# p7_1_3v3_-_Adafruit_Battery.net
KiCad netlist of a schematic drawn in EAGLE
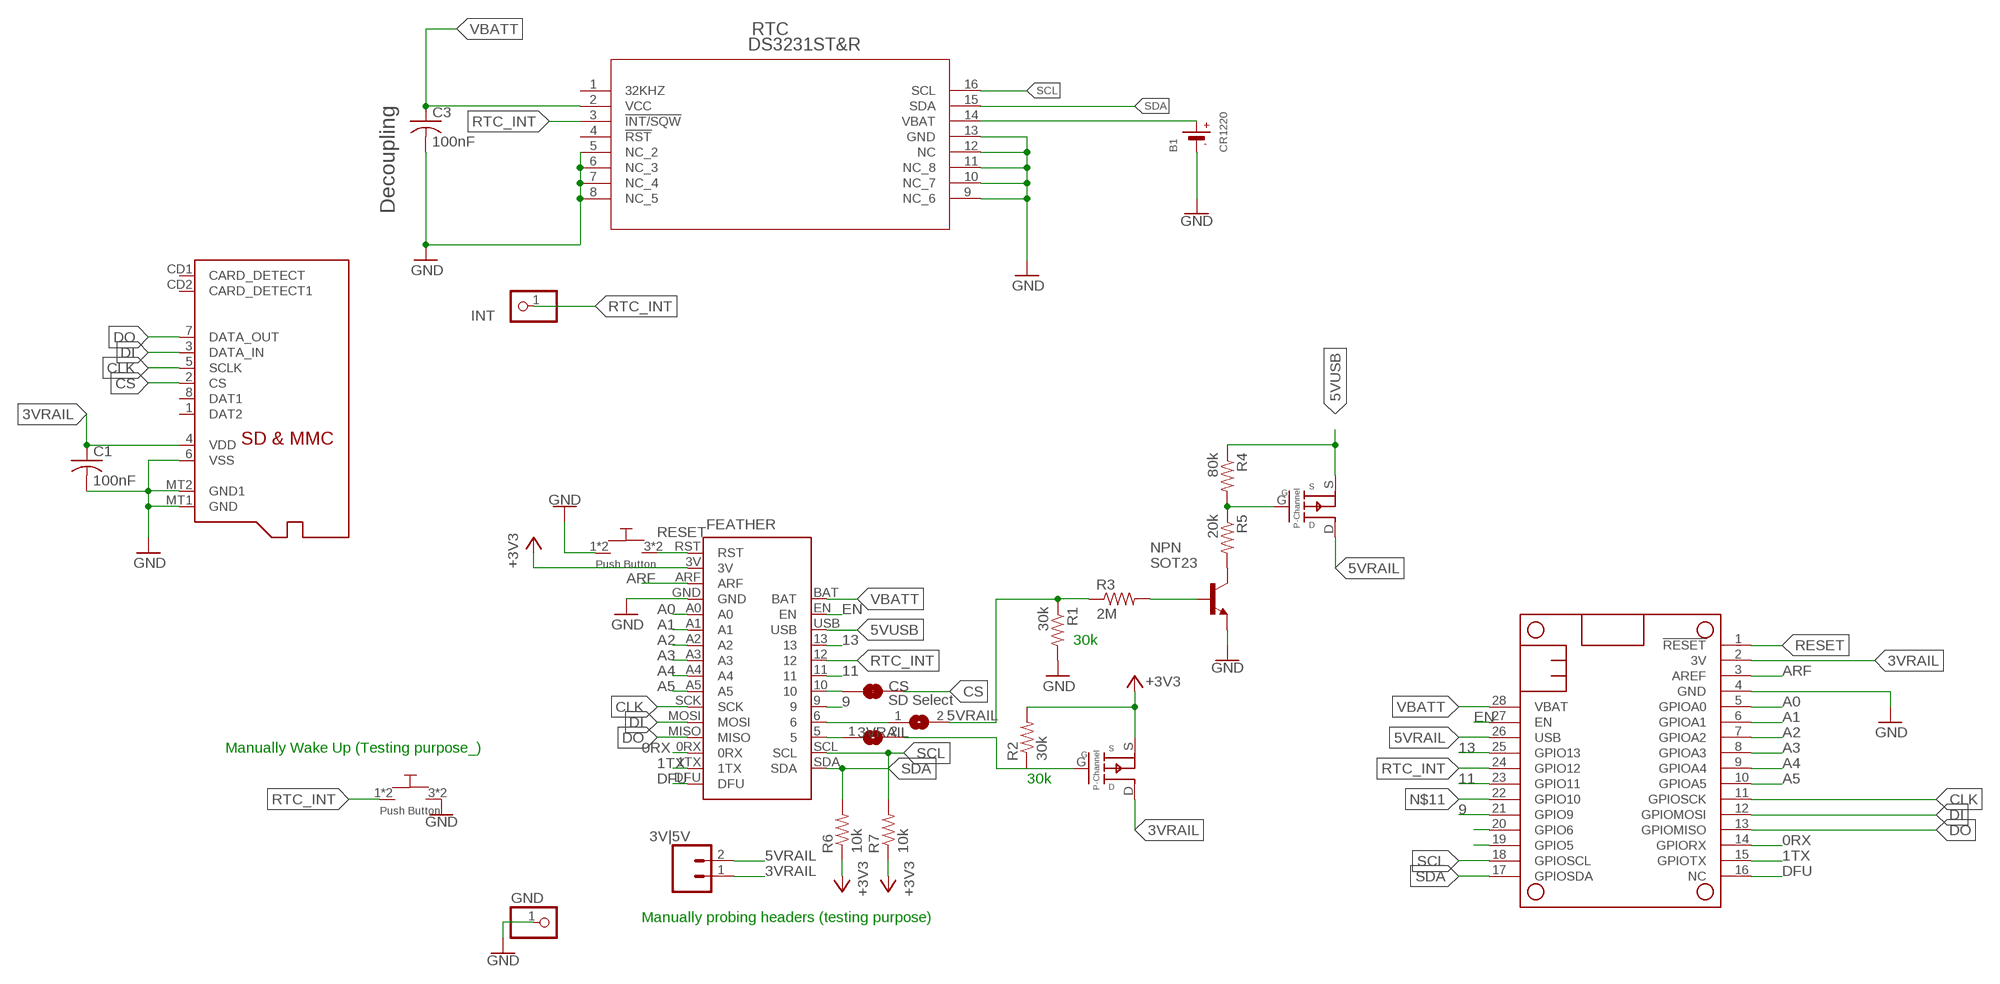
[diagram p0: schematic, sheet 1]

(export (version "E")
  (design (tool "Eeschema 10.0.6"))
  (components
    (comp (ref "3VRAIL")
      (value "SJ")
      (footprint "eagle-import:SJ")
      (libsource (lib "eagle-import") (part "SJ"))
    )
    (comp (ref "3V|5V")
      (value "CONN_021X02_NO_SILK")
      (footprint "eagle-import:1X02_NO_SILK")
      (libsource (lib "eagle-import") (part "CONN_021X02_NO_SILK"))
    )
    (comp (ref "5VRAIL")
      (value "SJ")
      (footprint "eagle-import:SJ")
      (libsource (lib "eagle-import") (part "SJ"))
    )
    (comp (ref "B1")
      (value "CR1220")
      (footprint "eagle-import:CR1220")
      (libsource (lib "eagle-import") (part "BATTERYCR1220_SMT"))
    )
    (comp (ref "C1")
      (value "100nF")
      (footprint "eagle-import:C1206")
      (libsource (lib "eagle-import") (part "C-USC1206"))
    )
    (comp (ref "C3")
      (value "100nF")
      (footprint "eagle-import:C1206")
      (libsource (lib "eagle-import") (part "C-USC1206"))
    )
    (comp (ref "CS")
      (value "SD Select")
      (footprint "eagle-import:SMT-JUMPER_2_NC_TRACE_SILK")
      (libsource (lib "eagle-import") (part "JUMPER-SMT_2_NC_TRACE_SILK"))
    )
    (comp (ref "FEATHER")
      (value "BLUEFRUIT_M0")
      (footprint "eagle-import:BLUEFRUIT_MO")
      (libsource (lib "eagle-import") (part "BLUEFRUIT_M0"))
    )
    (comp (ref "GND")
      (value "PINHD-1X1")
      (footprint "eagle-import:1X01")
      (libsource (lib "eagle-import") (part "adafruitmodified_PINHD-1X1"))
    )
    (comp (ref "INT")
      (value "PINHD-1X1CB")
      (footprint "eagle-import:1X01-CLEANBIG")
      (libsource (lib "eagle-import") (part "PINHD-1X1CB"))
    )
    (comp (ref "MICROSD")
      (value "MICROSD")
      (footprint "eagle-import:MICROSD")
      (libsource (lib "eagle-import") (part "MICROSD"))
    )
    (comp (ref "MS1")
      (value "FEATHERWING")
      (footprint "eagle-import:FEATHERWING")
      (libsource (lib "eagle-import") (part "FEATHERWING"))
    )
    (comp (ref "NPN")
      (value "SOT23")
      (footprint "eagle-import:SOT23")
      (libsource (lib "eagle-import") (part "BC849"))
    )
    (comp (ref "PMOS1")
      (value "SSM3J3228R")
      (footprint "eagle-import:SOT-23-3")
      (libsource (lib "eagle-import") (part "SSM3J3228R"))
    )
    (comp (ref "PMOS2")
      (value "SSM3J3228R")
      (footprint "eagle-import:SOT-23-3")
      (libsource (lib "eagle-import") (part "SSM3J3228R"))
    )
    (comp (ref "R1")
      (value "30k")
      (footprint "eagle-import:R1206")
      (libsource (lib "eagle-import") (part "R-US_R1206"))
    )
    (comp (ref "R2")
      (value "30k")
      (footprint "eagle-import:R1206")
      (libsource (lib "eagle-import") (part "R-US_R1206"))
    )
    (comp (ref "R3")
      (value "2M")
      (footprint "eagle-import:R1206")
      (libsource (lib "eagle-import") (part "R-US_R1206"))
    )
    (comp (ref "R4")
      (value "80k")
      (footprint "eagle-import:R1206")
      (libsource (lib "eagle-import") (part "R-US_R1206"))
    )
    (comp (ref "R5")
      (value "20k")
      (footprint "eagle-import:R1206")
      (libsource (lib "eagle-import") (part "R-US_R1206"))
    )
    (comp (ref "R6")
      (value "10k")
      (footprint "eagle-import:R1206")
      (libsource (lib "eagle-import") (part "R-US_R1206"))
    )
    (comp (ref "R7")
      (value "10k")
      (footprint "eagle-import:R1206")
      (libsource (lib "eagle-import") (part "R-US_R1206"))
    )
    (comp (ref "RTC")
      (value "DS3231ST&R")
      (footprint "eagle-import:21-0042B_16")
      (fields (field (name "MANUFACTURER_PART_NUMBER") "DS3231S#T&R"))
      (libsource (lib "eagle-import") (part "DS3231ST&R"))
    )
    (comp (ref "U$1")
      (value "PUSH_BUTTON")
      (footprint "eagle-import:PUSHBUTTON_SMD")
      (libsource (lib "eagle-import") (part "PUSH_BUTTON"))
    )
    (comp (ref "U$2")
      (value "PUSH_BUTTON")
      (footprint "eagle-import:PUSHBUTTON_SMD")
      (libsource (lib "eagle-import") (part "PUSH_BUTTON"))
    )
  )
  (nets
    (net (code "1") (name "+3V3") (class "Default")
      (node (ref "FEATHER") (pin "3V") (pinfunction "3V_3V") (pintype "bidirectional"))
      (node (ref "PMOS2") (pin "S") (pinfunction "S_S") (pintype "bidirectional"))
      (node (ref "R2") (pin "2") (pinfunction "2_2") (pintype "passive"))
      (node (ref "R6") (pin "1") (pinfunction "1_1") (pintype "passive"))
      (node (ref "R7") (pin "1") (pinfunction "1_1") (pintype "passive"))
    )
    (net (code "2") (name "/0RX") (class "Default")
      (node (ref "FEATHER") (pin "0RX") (pinfunction "0RX_0RX") (pintype "bidirectional"))
      (node (ref "MS1") (pin "14") (pinfunction "GPIORX_14") (pintype "bidirectional"))
    )
    (net (code "3") (name "/1TX") (class "Default")
      (node (ref "FEATHER") (pin "1TX") (pinfunction "1TX_1TX") (pintype "bidirectional"))
      (node (ref "MS1") (pin "15") (pinfunction "GPIOTX_15") (pintype "bidirectional"))
    )
    (net (code "4") (name "/9") (class "Default")
      (node (ref "FEATHER") (pin "9") (pinfunction "9_9") (pintype "bidirectional"))
      (node (ref "MS1") (pin "21") (pinfunction "GPIO9_21") (pintype "bidirectional"))
    )
    (net (code "5") (name "/11") (class "Default")
      (node (ref "FEATHER") (pin "11") (pinfunction "11_11") (pintype "bidirectional"))
      (node (ref "MS1") (pin "23") (pinfunction "GPIO11_23") (pintype "bidirectional"))
    )
    (net (code "6") (name "/13") (class "Default")
      (node (ref "FEATHER") (pin "13") (pinfunction "13_13") (pintype "bidirectional"))
      (node (ref "MS1") (pin "25") (pinfunction "GPIO13_25") (pintype "bidirectional"))
    )
    (net (code "7") (name "/A0") (class "Default")
      (node (ref "FEATHER") (pin "A0") (pinfunction "A0_A0") (pintype "bidirectional"))
      (node (ref "MS1") (pin "5") (pinfunction "GPIOA0_5") (pintype "bidirectional"))
    )
    (net (code "8") (name "/A1") (class "Default")
      (node (ref "FEATHER") (pin "A1") (pinfunction "A1_A1") (pintype "bidirectional"))
      (node (ref "MS1") (pin "6") (pinfunction "GPIOA1_6") (pintype "bidirectional"))
    )
    (net (code "9") (name "/A2") (class "Default")
      (node (ref "FEATHER") (pin "A2") (pinfunction "A2_A2") (pintype "bidirectional"))
      (node (ref "MS1") (pin "7") (pinfunction "GPIOA2_7") (pintype "bidirectional"))
    )
    (net (code "10") (name "/A3") (class "Default")
      (node (ref "FEATHER") (pin "A3") (pinfunction "A3_A3") (pintype "bidirectional"))
      (node (ref "MS1") (pin "8") (pinfunction "GPIOA3_8") (pintype "bidirectional"))
    )
    (net (code "11") (name "/A4") (class "Default")
      (node (ref "FEATHER") (pin "A4") (pinfunction "A4_A4") (pintype "bidirectional"))
      (node (ref "MS1") (pin "9") (pinfunction "GPIOA4_9") (pintype "bidirectional"))
    )
    (net (code "12") (name "/A5") (class "Default")
      (node (ref "FEATHER") (pin "A5") (pinfunction "A5_A5") (pintype "bidirectional"))
      (node (ref "MS1") (pin "10") (pinfunction "GPIOA5_10") (pintype "bidirectional"))
    )
    (net (code "13") (name "/ARF") (class "Default")
      (node (ref "FEATHER") (pin "ARF") (pinfunction "ARF_ARF") (pintype "bidirectional"))
      (node (ref "MS1") (pin "3") (pinfunction "AREF_3") (pintype "passive"))
    )
    (net (code "14") (name "/DFU") (class "Default")
      (node (ref "FEATHER") (pin "DFU") (pinfunction "DFU_DFU") (pintype "bidirectional"))
      (node (ref "MS1") (pin "16") (pinfunction "NC_16") (pintype "passive"))
    )
    (net (code "15") (name "/EN") (class "Default")
      (node (ref "FEATHER") (pin "EN") (pinfunction "EN_EN") (pintype "bidirectional"))
      (node (ref "MS1") (pin "27") (pinfunction "EN_27") (pintype "passive"))
    )
    (net (code "16") (name "3VRAIL") (class "Default")
      (node (ref "3V|5V") (pin "1") (pinfunction "1_1") (pintype "passive"))
      (node (ref "C1") (pin "1") (pinfunction "1_1") (pintype "passive"))
      (node (ref "MICROSD") (pin "4") (pinfunction "VDD_4") (pintype "power_in"))
      (node (ref "MS1") (pin "2") (pinfunction "3V_2") (pintype "power_in"))
      (node (ref "PMOS2") (pin "D") (pinfunction "D_D") (pintype "bidirectional"))
    )
    (net (code "17") (name "5VRAIL") (class "Default")
      (node (ref "3V|5V") (pin "2") (pinfunction "2_2") (pintype "passive"))
      (node (ref "MS1") (pin "26") (pinfunction "USB_26") (pintype "power_in"))
      (node (ref "PMOS1") (pin "D") (pinfunction "D_D") (pintype "bidirectional"))
    )
    (net (code "18") (name "5VUSB") (class "Default")
      (node (ref "FEATHER") (pin "USB") (pinfunction "USB_USB") (pintype "bidirectional"))
      (node (ref "PMOS1") (pin "S") (pinfunction "S_S") (pintype "bidirectional"))
      (node (ref "R4") (pin "1") (pinfunction "1_1") (pintype "passive"))
    )
    (net (code "19") (name "CLK") (class "Default")
      (node (ref "FEATHER") (pin "SCK") (pinfunction "SCK_SCK") (pintype "bidirectional"))
      (node (ref "MICROSD") (pin "5") (pinfunction "SCLK_5") (pintype "input"))
      (node (ref "MS1") (pin "11") (pinfunction "GPIOSCK_11") (pintype "bidirectional"))
    )
    (net (code "20") (name "CS") (class "Default")
      (node (ref "CS") (pin "2") (pinfunction "2_2") (pintype "passive"))
      (node (ref "MICROSD") (pin "2") (pinfunction "CS_2") (pintype "input"))
    )
    (net (code "21") (name "DI") (class "Default")
      (node (ref "FEATHER") (pin "MOSI") (pinfunction "MOSI_MOSI") (pintype "bidirectional"))
      (node (ref "MICROSD") (pin "3") (pinfunction "DATA_IN_3") (pintype "input"))
      (node (ref "MS1") (pin "12") (pinfunction "GPIOMOSI_12") (pintype "bidirectional"))
    )
    (net (code "22") (name "DO") (class "Default")
      (node (ref "FEATHER") (pin "MISO") (pinfunction "MISO_MISO") (pintype "bidirectional"))
      (node (ref "MICROSD") (pin "7") (pinfunction "DATA_OUT_7") (pintype "output"))
      (node (ref "MS1") (pin "13") (pinfunction "GPIOMISO_13") (pintype "bidirectional"))
    )
    (net (code "23") (name "GND") (class "Default")
      (node (ref "B1") (pin "-") (pinfunction "-_-") (pintype "passive"))
      (node (ref "C1") (pin "2") (pinfunction "2_2") (pintype "passive"))
      (node (ref "C3") (pin "2") (pinfunction "2_2") (pintype "passive"))
      (node (ref "FEATHER") (pin "GND") (pinfunction "GND_GND") (pintype "bidirectional"))
      (node (ref "GND") (pin "1") (pinfunction "1_1") (pintype "passive"))
      (node (ref "MICROSD") (pin "6") (pinfunction "VSS_6") (pintype "power_in"))
      (node (ref "MICROSD") (pin "MT1") (pinfunction "GND_MT1") (pintype "power_in"))
      (node (ref "MICROSD") (pin "MT2") (pinfunction "GND1_MT2") (pintype "power_in"))
      (node (ref "MS1") (pin "4") (pinfunction "GND_4") (pintype "power_in"))
      (node (ref "NPN") (pin "2") (pinfunction "E_2") (pintype "passive"))
      (node (ref "R1") (pin "2") (pinfunction "2_2") (pintype "passive"))
      (node (ref "RTC") (pin "10") (pinfunction "NC_7_10") (pintype "passive"))
      (node (ref "RTC") (pin "11") (pinfunction "NC_8_11") (pintype "passive"))
      (node (ref "RTC") (pin "12") (pinfunction "NC_12") (pintype "passive"))
      (node (ref "RTC") (pin "13") (pinfunction "GND_13") (pintype "power_in"))
      (node (ref "RTC") (pin "5") (pinfunction "NC_2_5") (pintype "passive"))
      (node (ref "RTC") (pin "6") (pinfunction "NC_3_6") (pintype "passive"))
      (node (ref "RTC") (pin "7") (pinfunction "NC_4_7") (pintype "passive"))
      (node (ref "RTC") (pin "8") (pinfunction "NC_5_8") (pintype "passive"))
      (node (ref "RTC") (pin "9") (pinfunction "NC_6_9") (pintype "passive"))
      (node (ref "U$1") (pin "1") (pinfunction "P$1_1") (pintype "bidirectional"))
      (node (ref "U$1") (pin "2") (pinfunction "P$1_2") (pintype "bidirectional"))
      (node (ref "U$2") (pin "3") (pinfunction "P$2_3") (pintype "bidirectional"))
      (node (ref "U$2") (pin "4") (pinfunction "P$2_4") (pintype "bidirectional"))
    )
    (net (code "24") (name "N$11") (class "Default")
      (node (ref "CS") (pin "1") (pinfunction "1_1") (pintype "passive"))
      (node (ref "FEATHER") (pin "10") (pinfunction "10_10") (pintype "bidirectional"))
      (node (ref "MS1") (pin "22") (pinfunction "GPIO10_22") (pintype "bidirectional"))
    )
    (net (code "25") (name "Net-(3VRAIL-Pad1)") (class "Default")
      (node (ref "3VRAIL") (pin "1") (pinfunction "1_1") (pintype "passive"))
      (node (ref "FEATHER") (pin "5") (pinfunction "5_5") (pintype "bidirectional"))
    )
    (net (code "26") (name "Net-(3VRAIL-Pad2)") (class "Default")
      (node (ref "3VRAIL") (pin "2") (pinfunction "2_2") (pintype "passive"))
      (node (ref "PMOS2") (pin "G") (pinfunction "G_G") (pintype "bidirectional"))
      (node (ref "R2") (pin "1") (pinfunction "1_1") (pintype "passive"))
    )
    (net (code "27") (name "Net-(5VRAIL-Pad1)") (class "Default")
      (node (ref "5VRAIL") (pin "1") (pinfunction "1_1") (pintype "passive"))
      (node (ref "FEATHER") (pin "6") (pinfunction "6_6") (pintype "bidirectional"))
    )
    (net (code "28") (name "Net-(5VRAIL-Pad2)") (class "Default")
      (node (ref "5VRAIL") (pin "2") (pinfunction "2_2") (pintype "passive"))
      (node (ref "R1") (pin "1") (pinfunction "1_1") (pintype "passive"))
      (node (ref "R3") (pin "1") (pinfunction "1_1") (pintype "passive"))
    )
    (net (code "29") (name "Net-(B1-+)") (class "Default")
      (node (ref "B1") (pin "+$1") (pinfunction "+_+$1") (pintype "passive"))
      (node (ref "RTC") (pin "14") (pinfunction "VBAT_14") (pintype "power_in"))
    )
    (net (code "30") (name "Net-(NPN-B)") (class "Default")
      (node (ref "NPN") (pin "1") (pinfunction "B_1") (pintype "passive"))
      (node (ref "R3") (pin "2") (pinfunction "2_2") (pintype "passive"))
    )
    (net (code "31") (name "Net-(NPN-C)") (class "Default")
      (node (ref "NPN") (pin "3") (pinfunction "C_3") (pintype "passive"))
      (node (ref "R5") (pin "2") (pinfunction "2_2") (pintype "passive"))
    )
    (net (code "32") (name "Net-(PMOS1-PadG)") (class "Default")
      (node (ref "PMOS1") (pin "G") (pinfunction "G_G") (pintype "bidirectional"))
      (node (ref "R4") (pin "2") (pinfunction "2_2") (pintype "passive"))
      (node (ref "R5") (pin "1") (pinfunction "1_1") (pintype "passive"))
    )
    (net (code "33") (name "RESET") (class "Default")
      (node (ref "FEATHER") (pin "RST") (pinfunction "RST_RST") (pintype "bidirectional"))
      (node (ref "MS1") (pin "1") (pinfunction "~{RESET}_1") (pintype "input"))
      (node (ref "U$1") (pin "3") (pinfunction "P$2_3") (pintype "bidirectional"))
      (node (ref "U$1") (pin "4") (pinfunction "P$2_4") (pintype "bidirectional"))
    )
    (net (code "34") (name "RTC_INT") (class "Default")
      (node (ref "FEATHER") (pin "12") (pinfunction "12_12") (pintype "bidirectional"))
      (node (ref "INT") (pin "1") (pinfunction "1_1") (pintype "passive"))
      (node (ref "MS1") (pin "24") (pinfunction "GPIO12_24") (pintype "bidirectional"))
      (node (ref "RTC") (pin "3") (pinfunction "~{INT/SQW}_3") (pintype "passive"))
      (node (ref "U$2") (pin "1") (pinfunction "P$1_1") (pintype "bidirectional"))
      (node (ref "U$2") (pin "2") (pinfunction "P$1_2") (pintype "bidirectional"))
    )
    (net (code "35") (name "SCL") (class "Default")
      (node (ref "FEATHER") (pin "SCL") (pinfunction "SCL_SCL") (pintype "bidirectional"))
      (node (ref "MS1") (pin "18") (pinfunction "GPIOSCL_18") (pintype "bidirectional"))
      (node (ref "R7") (pin "2") (pinfunction "2_2") (pintype "passive"))
      (node (ref "RTC") (pin "16") (pinfunction "SCL_16") (pintype "passive"))
    )
    (net (code "36") (name "SDA") (class "Default")
      (node (ref "FEATHER") (pin "SDA") (pinfunction "SDA_SDA") (pintype "bidirectional"))
      (node (ref "MS1") (pin "17") (pinfunction "GPIOSDA_17") (pintype "bidirectional"))
      (node (ref "R6") (pin "2") (pinfunction "2_2") (pintype "passive"))
      (node (ref "RTC") (pin "15") (pinfunction "SDA_15") (pintype "passive"))
    )
    (net (code "37") (name "VBATT") (class "Default")
      (node (ref "C3") (pin "1") (pinfunction "1_1") (pintype "passive"))
      (node (ref "FEATHER") (pin "BAT") (pinfunction "BAT_BAT") (pintype "bidirectional"))
      (node (ref "MS1") (pin "28") (pinfunction "VBAT_28") (pintype "power_in"))
      (node (ref "RTC") (pin "2") (pinfunction "VCC_2") (pintype "power_in"))
    )
    (net (code "38") (name "unconnected-(MICROSD-CARD_DETECT-PadCD1)") (class "Default")
      (node (ref "MICROSD") (pin "CD1") (pinfunction "CARD_DETECT_CD1") (pintype "passive"))
    )
    (net (code "39") (name "unconnected-(MICROSD-CARD_DETECT1-PadCD2)") (class "Default")
      (node (ref "MICROSD") (pin "CD2") (pinfunction "CARD_DETECT1_CD2") (pintype "passive"))
    )
    (net (code "40") (name "unconnected-(MICROSD-DAT1-Pad8)") (class "Default")
      (node (ref "MICROSD") (pin "8") (pinfunction "DAT1_8") (pintype "bidirectional"))
    )
    (net (code "41") (name "unconnected-(MICROSD-DAT2-Pad1)") (class "Default")
      (node (ref "MICROSD") (pin "1") (pinfunction "DAT2_1") (pintype "bidirectional"))
    )
    (net (code "42") (name "unconnected-(MS1-GPIO5-Pad19)") (class "Default")
      (node (ref "MS1") (pin "19") (pinfunction "GPIO5_19") (pintype "bidirectional"))
    )
    (net (code "43") (name "unconnected-(MS1-GPIO6-Pad20)") (class "Default")
      (node (ref "MS1") (pin "20") (pinfunction "GPIO6_20") (pintype "bidirectional"))
    )
    (net (code "44") (name "unconnected-(RTC-32KHZ-Pad1)") (class "Default")
      (node (ref "RTC") (pin "1") (pinfunction "32KHZ_1") (pintype "passive"))
    )
    (net (code "45") (name "unconnected-(RTC-~{RST}-Pad4)") (class "Default")
      (node (ref "RTC") (pin "4") (pinfunction "~{RST}_4") (pintype "passive"))
    )
  )
)
